# Candunio.net
KiCad netlist of a schematic drawn in Altium Designer
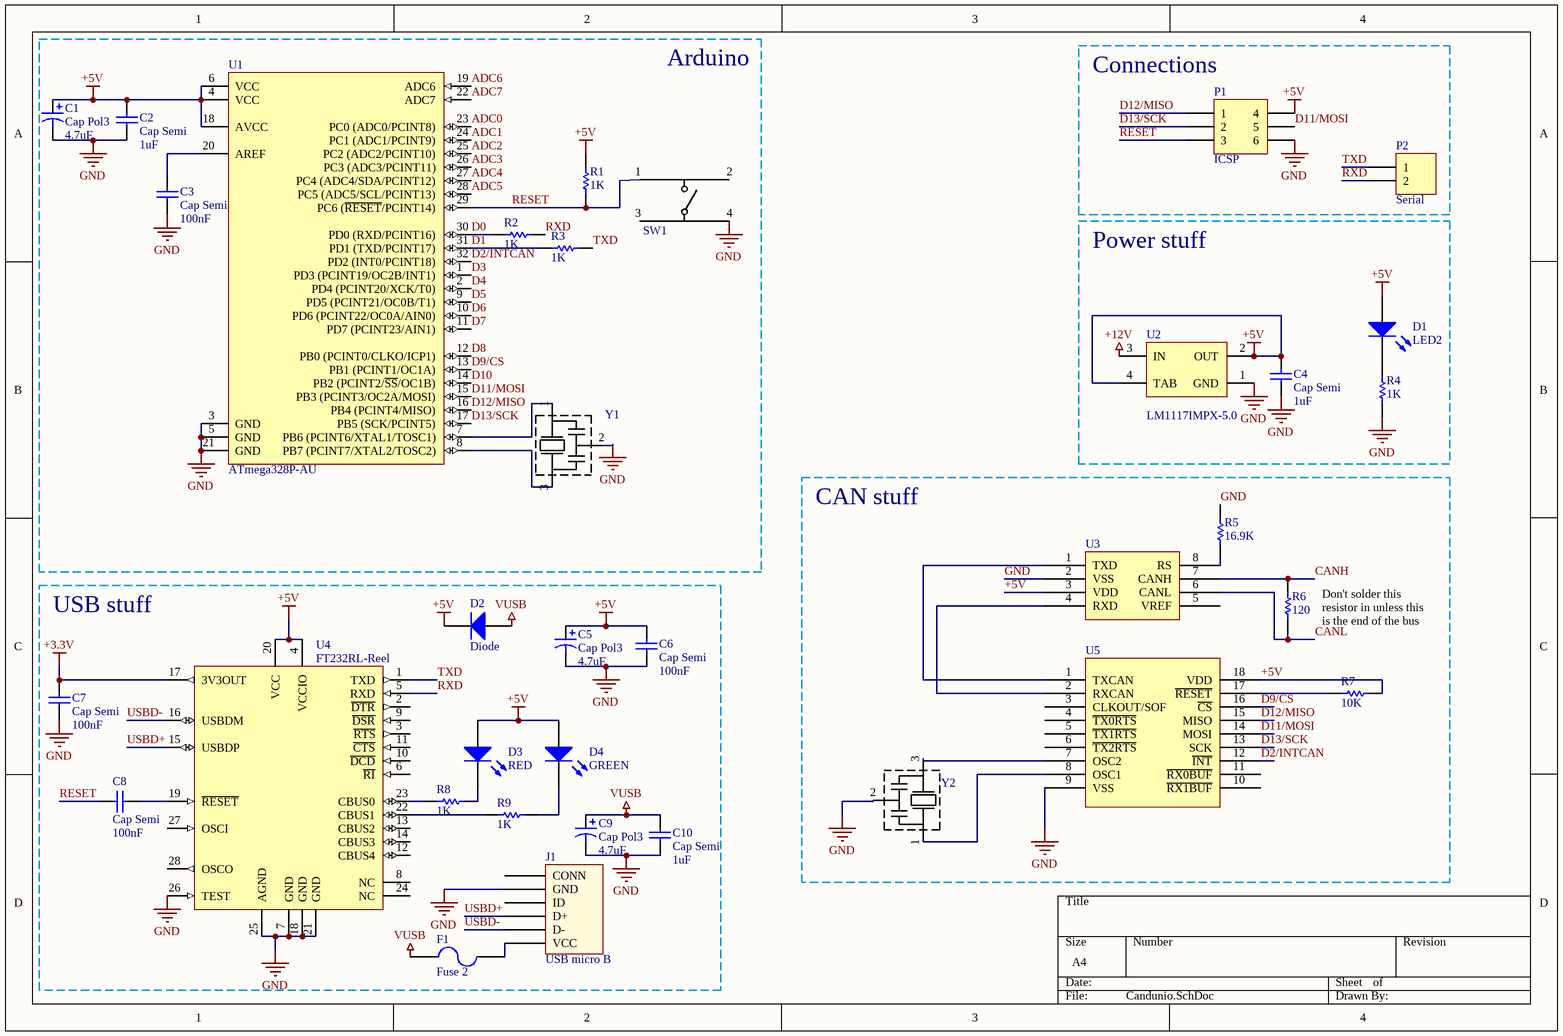
[diagram p0: Candunio.SchDoc]

(export (version "E")
  (design (tool "Eeschema 10.0.6"))
  (components
    (comp (ref "C1")
      (value "Cap Pol3")
      (footprint "C1206")
      (description "Polarized Capacitor (Surface Mount)")
      (fields (field (name "ALTIUM_VALUE") "4.7uF") (field (name "PUBLISHER") "Altium Limited"))
      (libsource (lib "Miscellaneous Devices") (part "Cap Pol3"))
    )
    (comp (ref "C2")
      (value "Cap Semi")
      (footprint "C1206")
      (description "Capacitor (Semiconductor SIM Model)")
      (fields (field (name "ALTIUM_VALUE") "1uF") (field (name "PUBLISHER") "Altium Limited"))
      (libsource (lib "Miscellaneous Devices") (part "Cap Semi"))
    )
    (comp (ref "C3")
      (value "Cap Semi")
      (footprint "C1206")
      (description "Capacitor (Semiconductor SIM Model)")
      (fields (field (name "ALTIUM_VALUE") "100nF") (field (name "PUBLISHER") "Altium Limited"))
      (libsource (lib "Miscellaneous Devices") (part "Cap Semi"))
    )
    (comp (ref "C4")
      (value "Cap Semi")
      (footprint "C1206")
      (description "Capacitor (Semiconductor SIM Model)")
      (fields (field (name "ALTIUM_VALUE") "1uF") (field (name "PUBLISHER") "Altium Limited"))
      (libsource (lib "Miscellaneous Devices") (part "Cap Semi"))
    )
    (comp (ref "C5")
      (value "Cap Pol3")
      (footprint "C1206")
      (description "Polarized Capacitor (Surface Mount)")
      (fields (field (name "ALTIUM_VALUE") "4.7uF") (field (name "PUBLISHER") "Altium Limited"))
      (libsource (lib "Miscellaneous Devices") (part "Cap Pol3"))
    )
    (comp (ref "C6")
      (value "Cap Semi")
      (footprint "C1206")
      (description "Capacitor (Semiconductor SIM Model)")
      (fields (field (name "ALTIUM_VALUE") "100nF") (field (name "PUBLISHER") "Altium Limited"))
      (libsource (lib "Miscellaneous Devices") (part "Cap Semi"))
    )
    (comp (ref "C7")
      (value "Cap Semi")
      (footprint "C1206")
      (description "Capacitor (Semiconductor SIM Model)")
      (fields (field (name "ALTIUM_VALUE") "100nF") (field (name "PUBLISHER") "Altium Limited"))
      (libsource (lib "Miscellaneous Devices") (part "Cap Semi"))
    )
    (comp (ref "C8")
      (value "Cap Semi")
      (footprint "C1206")
      (description "Capacitor (Semiconductor SIM Model)")
      (fields (field (name "ALTIUM_VALUE") "100nF") (field (name "PUBLISHER") "Altium Limited"))
      (libsource (lib "Miscellaneous Devices") (part "Cap Semi"))
    )
    (comp (ref "C9")
      (value "Cap Pol3")
      (footprint "C1206")
      (description "Polarized Capacitor (Surface Mount)")
      (fields (field (name "ALTIUM_VALUE") "4.7uF") (field (name "PUBLISHER") "Altium Limited"))
      (libsource (lib "Miscellaneous Devices") (part "Cap Pol3"))
    )
    (comp (ref "C10")
      (value "Cap Semi")
      (footprint "C1206")
      (description "Capacitor (Semiconductor SIM Model)")
      (fields (field (name "ALTIUM_VALUE") "1uF") (field (name "PUBLISHER") "Altium Limited"))
      (libsource (lib "Miscellaneous Devices") (part "Cap Semi"))
    )
    (comp (ref "D1")
      (value "LED2")
      (footprint "3.2X1.6X1.1")
      (description "Typical RED, GREEN, YELLOW, AMBER GaAs LED")
      (fields (field (name "PUBLISHER") "Altium Limited"))
      (libsource (lib "Miscellaneous Devices") (part "LED2"))
    )
    (comp (ref "D2")
      (value "Diode")
      (footprint "SMC")
      (description "Default Diode")
      (fields (field (name "PUBLISHER") "Altium Limited"))
      (libsource (lib "Miscellaneous Devices") (part "Diode"))
    )
    (comp (ref "D3")
      (value "RED")
      (footprint "3.2X1.6X1.1")
      (description "Typical RED, GREEN, YELLOW, AMBER GaAs LED")
      (fields (field (name "PUBLISHER") "Altium Limited"))
      (libsource (lib "Miscellaneous Devices") (part "LED2"))
    )
    (comp (ref "D4")
      (value "GREEN")
      (footprint "3.2X1.6X1.1")
      (description "Typical RED, GREEN, YELLOW, AMBER GaAs LED")
      (fields (field (name "PUBLISHER") "Altium Limited"))
      (libsource (lib "Miscellaneous Devices") (part "LED2"))
    )
    (comp (ref "F1")
      (value "Fuse 2")
      (footprint "1812")
      (description "Fuse")
      (fields (field (name "PART NUMBER") "MF-MSMF050-2") (field (name "PUBLISHER") "Altium Limited"))
      (libsource (lib "Miscellaneous Devices") (part "Fuse 2"))
    )
    (comp (ref "J1")
      (value "USB micro B")
      (footprint "1050170001")
      (description "CONN SM TH USB MICRO MODIFIED FOR DRILL")
      (fields (field (name "PART NUMBER") "WM1399CT-ND"))
      (libsource (lib "electronpowered") (part "1050170001"))
    )
    (comp (ref "P1")
      (value "ICSP")
      (footprint "HDR2X3_CEN")
      (description "Header, 3-Pin, Dual row")
      (fields (field (name "PUBLISHER") "Altium Limited"))
      (libsource (lib "Miscellaneous Connectors") (part "Header 3X2A"))
    )
    (comp (ref "P2")
      (value "Serial")
      (footprint "HDR1X2")
      (description "Header, 2-Pin")
      (fields (field (name "PUBLISHER") "Altium Limited"))
      (libsource (lib "Miscellaneous Connectors") (part "Header 2"))
    )
    (comp (ref "R1")
      (value "1K")
      (footprint "14-1210")
      (description "Resistor")
      (libsource (lib "Miscellaneous Devices") (part "Res1"))
    )
    (comp (ref "R2")
      (value "1K")
      (footprint "14-1210")
      (description "Resistor")
      (libsource (lib "Miscellaneous Devices") (part "Res1"))
    )
    (comp (ref "R3")
      (value "1K")
      (footprint "14-1210")
      (description "Resistor")
      (libsource (lib "Miscellaneous Devices") (part "Res1"))
    )
    (comp (ref "R4")
      (value "1K")
      (footprint "14-1210")
      (description "Resistor")
      (libsource (lib "Miscellaneous Devices") (part "Res1"))
    )
    (comp (ref "R5")
      (value "16.9K")
      (footprint "14-1210")
      (description "Resistor")
      (libsource (lib "Miscellaneous Devices") (part "Res1"))
    )
    (comp (ref "R6")
      (value "120")
      (footprint "14-1210")
      (description "Resistor")
      (libsource (lib "Miscellaneous Devices") (part "Res1"))
    )
    (comp (ref "R7")
      (value "10K")
      (footprint "14-1210")
      (description "Resistor")
      (libsource (lib "Miscellaneous Devices") (part "Res1"))
    )
    (comp (ref "R8")
      (value "1K")
      (footprint "14-1210")
      (description "Resistor")
      (libsource (lib "Miscellaneous Devices") (part "Res1"))
    )
    (comp (ref "R9")
      (value "1K")
      (footprint "14-1210")
      (description "Resistor")
      (libsource (lib "Miscellaneous Devices") (part "Res1"))
    )
    (comp (ref "SW1")
      (value "PTS525SM15SMTR2")
      (footprint "PTS525SM15SMTR2")
      (libsource (lib "AMSComponents") (part "PTS525SM15SMTR2"))
    )
    (comp (ref "U1")
      (value "ATmega328P-AU")
      (footprint "32A_N")
      (fields (field (name "PUBLISHER") "Altium Limited"))
      (libsource (lib "Atmel Microcontroller 8-Bit megaAVR") (part "ATmega328P-AU"))
    )
    (comp (ref "U2")
      (value "LM1117IMPX-5.0")
      (footprint "MP04A_N")
      (description "800mA Low-Dropout Linear Regulator, 4-pin SOT-223")
      (fields
        (field (name "MANUFACTURER") "National Semiconductor")
        (field (name "PUBLISHER") "Altium Limited")
      )
      (libsource (lib "NSC LDO") (part "LM1117IMPX-5.0"))
    )
    (comp (ref "U3")
      (value "MCP2551-E/SN")
      (footprint "SOIC127P600X175-8M")
      (description "SOIC")
      (libsource (lib "AMSComponents") (part "MCP2551-E/SN"))
    )
    (comp (ref "U4")
      (value "FT232RL-Reel")
      (footprint "SSOP-28_N")
      (description "USB UART Asynchronous Serial Data Transfer Chip, SSOP-28, Tape and Reel")
      (fields (field (name "PUBLISHER") "Altium Limited"))
      (libsource (lib "FTDI Communication UART") (part "FT232RL-Reel"))
    )
    (comp (ref "U5")
      (value "MCP2515-E/ST")
      (footprint "SOIC127P1030X265-18M")
      (description "SOIC")
      (libsource (lib "AMSComponents") (part "MCP2515-E/ST"))
    )
    (comp (ref "Y1")
      (value "CSTCE16M0V53-R0")
      (footprint "CSTCE16M0V53-R0")
      (libsource (lib "AMSComponents") (part "CSTCE16M0V53-R0"))
    )
    (comp (ref "Y2")
      (value "CSTCE16M0V53-R0")
      (footprint "CSTCE16M0V53-R0")
      (libsource (lib "AMSComponents") (part "CSTCE16M0V53-R0"))
    )
  )
  (nets
    (net (code "1") (name "+3.3V") (class "Default")
      (node (ref "C7") (pin "1") (pinfunction "1_1") (pintype "passive"))
      (node (ref "U4") (pin "17") (pinfunction "3V3OUT_17") (pintype "output"))
    )
    (net (code "2") (name "+5V") (class "Default")
      (node (ref "C1") (pin "1") (pinfunction "1_1") (pintype "passive"))
      (node (ref "C2") (pin "1") (pinfunction "1_1") (pintype "passive"))
      (node (ref "C4") (pin "1") (pinfunction "1_1") (pintype "passive"))
      (node (ref "C5") (pin "1") (pinfunction "1_1") (pintype "passive"))
      (node (ref "C6") (pin "1") (pinfunction "1_1") (pintype "passive"))
      (node (ref "D1") (pin "1") (pinfunction "A_1") (pintype "passive"))
      (node (ref "D2") (pin "2") (pinfunction "K_2") (pintype "passive"))
      (node (ref "D3") (pin "1") (pinfunction "A_1") (pintype "passive"))
      (node (ref "D4") (pin "1") (pinfunction "A_1") (pintype "passive"))
      (node (ref "P1") (pin "4") (pinfunction "4_4") (pintype "passive"))
      (node (ref "R1") (pin "1") (pinfunction "1_1") (pintype "passive"))
      (node (ref "R7") (pin "2") (pinfunction "2_2") (pintype "passive"))
      (node (ref "U1") (pin "18") (pinfunction "AVCC_18") (pintype "power_in"))
      (node (ref "U1") (pin "4") (pinfunction "VCC_4") (pintype "power_in"))
      (node (ref "U1") (pin "6") (pinfunction "VCC_6") (pintype "power_in"))
      (node (ref "U2") (pin "2") (pinfunction "OUT_2") (pintype "power_in"))
      (node (ref "U2") (pin "4") (pinfunction "TAB_4") (pintype "power_in"))
      (node (ref "U3") (pin "3") (pinfunction "VDD_3") (pintype "passive"))
      (node (ref "U4") (pin "20") (pinfunction "VCC_20") (pintype "power_in"))
      (node (ref "U4") (pin "4") (pinfunction "VCCIO_4") (pintype "power_in"))
      (node (ref "U5") (pin "18") (pinfunction "VDD_18") (pintype "passive"))
    )
    (net (code "3") (name "+12V") (class "Default")
      (node (ref "U2") (pin "3") (pinfunction "IN_3") (pintype "power_in"))
    )
    (net (code "4") (name "/ADC0") (class "Default")
      (node (ref "U1") (pin "23") (pinfunction "PC0_(ADC0/PCINT8)_23") (pintype "bidirectional"))
    )
    (net (code "5") (name "/ADC1") (class "Default")
      (node (ref "U1") (pin "24") (pinfunction "PC1_(ADC1/PCINT9)_24") (pintype "bidirectional"))
    )
    (net (code "6") (name "/ADC2") (class "Default")
      (node (ref "U1") (pin "25") (pinfunction "PC2_(ADC2/PCINT10)_25") (pintype "bidirectional"))
    )
    (net (code "7") (name "/ADC3") (class "Default")
      (node (ref "U1") (pin "26") (pinfunction "PC3_(ADC3/PCINT11)_26") (pintype "bidirectional"))
    )
    (net (code "8") (name "/ADC4") (class "Default")
      (node (ref "U1") (pin "27") (pinfunction "PC4_(ADC4/SDA/PCINT12)_27") (pintype "bidirectional"))
    )
    (net (code "9") (name "/ADC5") (class "Default")
      (node (ref "U1") (pin "28") (pinfunction "PC5_(ADC5/SCL/PCINT13)_28") (pintype "bidirectional"))
    )
    (net (code "10") (name "/ADC6") (class "Default")
      (node (ref "U1") (pin "19") (pinfunction "ADC6_19") (pintype "input"))
    )
    (net (code "11") (name "/ADC7") (class "Default")
      (node (ref "U1") (pin "22") (pinfunction "ADC7_22") (pintype "input"))
    )
    (net (code "12") (name "/CANH") (class "Default")
      (node (ref "R6") (pin "1") (pinfunction "1_1") (pintype "passive"))
      (node (ref "U3") (pin "7") (pinfunction "CANH_7") (pintype "passive"))
    )
    (net (code "13") (name "/CANL") (class "Default")
      (node (ref "R6") (pin "2") (pinfunction "2_2") (pintype "passive"))
      (node (ref "U3") (pin "6") (pinfunction "CANL_6") (pintype "passive"))
    )
    (net (code "14") (name "/D0") (class "Default")
      (node (ref "R2") (pin "1") (pinfunction "1_1") (pintype "passive"))
      (node (ref "U1") (pin "30") (pinfunction "PD0_(RXD/PCINT16)_30") (pintype "bidirectional"))
    )
    (net (code "15") (name "/D1") (class "Default")
      (node (ref "R3") (pin "1") (pinfunction "1_1") (pintype "passive"))
      (node (ref "U1") (pin "31") (pinfunction "PD1_(TXD/PCINT17)_31") (pintype "bidirectional"))
    )
    (net (code "16") (name "/D2{slash}INTCAN") (class "Default")
      (node (ref "U1") (pin "32") (pinfunction "PD2_(INT0/PCINT18)_32") (pintype "bidirectional"))
      (node (ref "U5") (pin "12") (pinfunction "~{INT}_12") (pintype "passive"))
    )
    (net (code "17") (name "/D3") (class "Default")
      (node (ref "U1") (pin "1") (pinfunction "PD3_(PCINT19/OC2B/INT1)_1") (pintype "bidirectional"))
    )
    (net (code "18") (name "/D4") (class "Default")
      (node (ref "U1") (pin "2") (pinfunction "PD4_(PCINT20/XCK/T0)_2") (pintype "bidirectional"))
    )
    (net (code "19") (name "/D5") (class "Default")
      (node (ref "U1") (pin "9") (pinfunction "PD5_(PCINT21/OC0B/T1)_9") (pintype "bidirectional"))
    )
    (net (code "20") (name "/D6") (class "Default")
      (node (ref "U1") (pin "10") (pinfunction "PD6_(PCINT22/OC0A/AIN0)_10") (pintype "bidirectional"))
    )
    (net (code "21") (name "/D7") (class "Default")
      (node (ref "U1") (pin "11") (pinfunction "PD7_(PCINT23/AIN1)_11") (pintype "bidirectional"))
    )
    (net (code "22") (name "/D8") (class "Default")
      (node (ref "U1") (pin "12") (pinfunction "PB0_(PCINT0/CLKO/ICP1)_12") (pintype "bidirectional"))
    )
    (net (code "23") (name "/D9{slash}CS") (class "Default")
      (node (ref "U1") (pin "13") (pinfunction "PB1_(PCINT1/OC1A)_13") (pintype "bidirectional"))
      (node (ref "U5") (pin "16") (pinfunction "~{CS}_16") (pintype "passive"))
    )
    (net (code "24") (name "/D10") (class "Default")
      (node (ref "U1") (pin "14") (pinfunction "PB2_(PCINT2/~{SS}/OC1B)_14") (pintype "bidirectional"))
    )
    (net (code "25") (name "/D11{slash}MOSI") (class "Default")
      (node (ref "P1") (pin "5") (pinfunction "5_5") (pintype "passive"))
      (node (ref "U1") (pin "15") (pinfunction "PB3_(PCINT3/OC2A/MOSI)_15") (pintype "bidirectional"))
      (node (ref "U5") (pin "14") (pinfunction "MOSI_14") (pintype "passive"))
    )
    (net (code "26") (name "/D12{slash}MISO") (class "Default")
      (node (ref "P1") (pin "1") (pinfunction "1_1") (pintype "passive"))
      (node (ref "U1") (pin "16") (pinfunction "PB4_(PCINT4/MISO)_16") (pintype "bidirectional"))
      (node (ref "U5") (pin "15") (pinfunction "MISO_15") (pintype "passive"))
    )
    (net (code "27") (name "/D13{slash}SCK") (class "Default")
      (node (ref "P1") (pin "2") (pinfunction "2_2") (pintype "passive"))
      (node (ref "U1") (pin "17") (pinfunction "PB5_(SCK/PCINT5)_17") (pintype "bidirectional"))
      (node (ref "U5") (pin "13") (pinfunction "SCK_13") (pintype "passive"))
    )
    (net (code "28") (name "/RESET") (class "Default")
      (node (ref "C8") (pin "1") (pinfunction "1_1") (pintype "passive"))
      (node (ref "P1") (pin "3") (pinfunction "3_3") (pintype "passive"))
      (node (ref "R1") (pin "2") (pinfunction "2_2") (pintype "passive"))
      (node (ref "SW1") (pin "1") (pinfunction "1_1") (pintype "passive"))
      (node (ref "U1") (pin "29") (pinfunction "PC6_(~{RESET}/PCINT14)_29") (pintype "bidirectional"))
    )
    (net (code "29") (name "/RXD") (class "Default")
      (node (ref "P2") (pin "2") (pinfunction "2_2") (pintype "passive"))
      (node (ref "R2") (pin "2") (pinfunction "2_2") (pintype "passive"))
      (node (ref "U4") (pin "5") (pinfunction "RXD_5") (pintype "input"))
    )
    (net (code "30") (name "/TXD") (class "Default")
      (node (ref "P2") (pin "1") (pinfunction "1_1") (pintype "passive"))
      (node (ref "R3") (pin "2") (pinfunction "2_2") (pintype "passive"))
      (node (ref "U4") (pin "1") (pinfunction "TXD_1") (pintype "output"))
    )
    (net (code "31") (name "/USBD+") (class "Default")
      (node (ref "J1") (pin "3") (pinfunction "D+_3") (pintype "passive"))
      (node (ref "U4") (pin "15") (pinfunction "USBDP_15") (pintype "bidirectional"))
    )
    (net (code "32") (name "/USBD-") (class "Default")
      (node (ref "J1") (pin "2") (pinfunction "D-_2") (pintype "passive"))
      (node (ref "U4") (pin "16") (pinfunction "USBDM_16") (pintype "bidirectional"))
    )
    (net (code "33") (name "GND") (class "Default")
      (node (ref "C1") (pin "2") (pinfunction "2_2") (pintype "passive"))
      (node (ref "C10") (pin "2") (pinfunction "2_2") (pintype "passive"))
      (node (ref "C2") (pin "2") (pinfunction "2_2") (pintype "passive"))
      (node (ref "C3") (pin "2") (pinfunction "2_2") (pintype "passive"))
      (node (ref "C4") (pin "2") (pinfunction "2_2") (pintype "passive"))
      (node (ref "C5") (pin "2") (pinfunction "2_2") (pintype "passive"))
      (node (ref "C6") (pin "2") (pinfunction "2_2") (pintype "passive"))
      (node (ref "C7") (pin "2") (pinfunction "2_2") (pintype "passive"))
      (node (ref "C9") (pin "2") (pinfunction "2_2") (pintype "passive"))
      (node (ref "J1") (pin "5") (pinfunction "GND_5") (pintype "passive"))
      (node (ref "P1") (pin "6") (pinfunction "6_6") (pintype "passive"))
      (node (ref "R4") (pin "2") (pinfunction "2_2") (pintype "passive"))
      (node (ref "R5") (pin "1") (pinfunction "1_1") (pintype "passive"))
      (node (ref "SW1") (pin "4") (pinfunction "4_4") (pintype "passive"))
      (node (ref "U1") (pin "21") (pinfunction "GND_21") (pintype "power_in"))
      (node (ref "U1") (pin "3") (pinfunction "GND_3") (pintype "power_in"))
      (node (ref "U1") (pin "5") (pinfunction "GND_5") (pintype "power_in"))
      (node (ref "U2") (pin "1") (pinfunction "GND_1") (pintype "power_in"))
      (node (ref "U3") (pin "2") (pinfunction "VSS_2") (pintype "passive"))
      (node (ref "U4") (pin "18") (pinfunction "GND_18") (pintype "power_in"))
      (node (ref "U4") (pin "21") (pinfunction "GND_21") (pintype "power_in"))
      (node (ref "U4") (pin "25") (pinfunction "AGND_25") (pintype "power_in"))
      (node (ref "U4") (pin "26") (pinfunction "TEST_26") (pintype "input"))
      (node (ref "U4") (pin "7") (pinfunction "GND_7") (pintype "power_in"))
      (node (ref "U5") (pin "9") (pinfunction "VSS_9") (pintype "passive"))
      (node (ref "Y1") (pin "2") (pinfunction "2_2") (pintype "passive"))
      (node (ref "Y2") (pin "2") (pinfunction "2_2") (pintype "passive"))
    )
    (net (code "34") (name "Net-(D1-K)") (class "Default")
      (node (ref "D1") (pin "2") (pinfunction "K_2") (pintype "passive"))
      (node (ref "R4") (pin "1") (pinfunction "1_1") (pintype "passive"))
    )
    (net (code "35") (name "Net-(D3-K)") (class "Default")
      (node (ref "D3") (pin "2") (pinfunction "K_2") (pintype "passive"))
      (node (ref "R8") (pin "2") (pinfunction "2_2") (pintype "passive"))
    )
    (net (code "36") (name "Net-(D4-K)") (class "Default")
      (node (ref "D4") (pin "2") (pinfunction "K_2") (pintype "passive"))
      (node (ref "R9") (pin "2") (pinfunction "2_2") (pintype "passive"))
    )
    (net (code "37") (name "Net-(J1-VCC)") (class "Default")
      (node (ref "F1") (pin "2") (pinfunction "2_2") (pintype "passive"))
      (node (ref "J1") (pin "1") (pinfunction "VCC_1") (pintype "passive"))
    )
    (net (code "38") (name "Net-(U1-AREF)") (class "Default")
      (node (ref "C3") (pin "1") (pinfunction "1_1") (pintype "passive"))
      (node (ref "U1") (pin "20") (pinfunction "AREF_20") (pintype "passive"))
    )
    (net (code "39") (name "Net-(U1-PB6_(PCINT6{slash}XTAL1{slash}TOSC1))") (class "Default")
      (node (ref "U1") (pin "7") (pinfunction "PB6_(PCINT6/XTAL1/TOSC1)_7") (pintype "bidirectional"))
      (node (ref "Y1") (pin "1") (pinfunction "1_1") (pintype "passive"))
    )
    (net (code "40") (name "Net-(U1-PB7_(PCINT7{slash}XTAL2{slash}TOSC2))") (class "Default")
      (node (ref "U1") (pin "8") (pinfunction "PB7_(PCINT7/XTAL2/TOSC2)_8") (pintype "bidirectional"))
      (node (ref "Y1") (pin "3") (pinfunction "3_3") (pintype "passive"))
    )
    (net (code "41") (name "Net-(U3-RS)") (class "Default")
      (node (ref "R5") (pin "2") (pinfunction "2_2") (pintype "passive"))
      (node (ref "U3") (pin "8") (pinfunction "RS_8") (pintype "passive"))
    )
    (net (code "42") (name "Net-(U3-RXD)") (class "Default")
      (node (ref "U3") (pin "4") (pinfunction "RXD_4") (pintype "passive"))
      (node (ref "U5") (pin "2") (pinfunction "RXCAN_2") (pintype "passive"))
    )
    (net (code "43") (name "Net-(U3-TXD)") (class "Default")
      (node (ref "U3") (pin "1") (pinfunction "TXD_1") (pintype "passive"))
      (node (ref "U5") (pin "1") (pinfunction "TXCAN_1") (pintype "passive"))
    )
    (net (code "44") (name "Net-(U4-CBUS0)") (class "Default")
      (node (ref "R8") (pin "1") (pinfunction "1_1") (pintype "passive"))
      (node (ref "U4") (pin "23") (pinfunction "CBUS0_23") (pintype "bidirectional"))
    )
    (net (code "45") (name "Net-(U4-CBUS1)") (class "Default")
      (node (ref "R9") (pin "1") (pinfunction "1_1") (pintype "passive"))
      (node (ref "U4") (pin "22") (pinfunction "CBUS1_22") (pintype "bidirectional"))
    )
    (net (code "46") (name "Net-(U4-~{RESET})") (class "Default")
      (node (ref "C8") (pin "2") (pinfunction "2_2") (pintype "passive"))
      (node (ref "U4") (pin "19") (pinfunction "~{RESET}_19") (pintype "input"))
    )
    (net (code "47") (name "Net-(U5-OSC1)") (class "Default")
      (node (ref "U5") (pin "8") (pinfunction "OSC1_8") (pintype "passive"))
      (node (ref "Y2") (pin "1") (pinfunction "1_1") (pintype "passive"))
    )
    (net (code "48") (name "Net-(U5-OSC2)") (class "Default")
      (node (ref "U5") (pin "7") (pinfunction "OSC2_7") (pintype "passive"))
      (node (ref "Y2") (pin "3") (pinfunction "3_3") (pintype "passive"))
    )
    (net (code "49") (name "Net-(U5-~{RESET})") (class "Default")
      (node (ref "R7") (pin "1") (pinfunction "1_1") (pintype "passive"))
      (node (ref "U5") (pin "17") (pinfunction "~{RESET}_17") (pintype "passive"))
    )
    (net (code "50") (name "VUSB") (class "Default")
      (node (ref "C10") (pin "1") (pinfunction "1_1") (pintype "passive"))
      (node (ref "C9") (pin "1") (pinfunction "1_1") (pintype "passive"))
      (node (ref "D2") (pin "1") (pinfunction "A_1") (pintype "passive"))
      (node (ref "F1") (pin "1") (pinfunction "1_1") (pintype "passive"))
    )
    (net (code "51") (name "unconnected-(J1-CONN-Pad0)") (class "Default")
      (node (ref "J1") (pin "0") (pinfunction "CONN_0") (pintype "passive"))
    )
    (net (code "52") (name "unconnected-(J1-ID-Pad4)") (class "Default")
      (node (ref "J1") (pin "4") (pinfunction "ID_4") (pintype "passive"))
    )
    (net (code "53") (name "unconnected-(SW1-Pad2)") (class "Default")
      (node (ref "SW1") (pin "2") (pinfunction "2_2") (pintype "passive"))
    )
    (net (code "54") (name "unconnected-(SW1-Pad3)") (class "Default")
      (node (ref "SW1") (pin "3") (pinfunction "3_3") (pintype "passive"))
    )
    (net (code "55") (name "unconnected-(U3-VREF-Pad5)") (class "Default")
      (node (ref "U3") (pin "5") (pinfunction "VREF_5") (pintype "passive"))
    )
    (net (code "56") (name "unconnected-(U4-CBUS2-Pad13)") (class "Default")
      (node (ref "U4") (pin "13") (pinfunction "CBUS2_13") (pintype "bidirectional"))
    )
    (net (code "57") (name "unconnected-(U4-CBUS3-Pad14)") (class "Default")
      (node (ref "U4") (pin "14") (pinfunction "CBUS3_14") (pintype "bidirectional"))
    )
    (net (code "58") (name "unconnected-(U4-CBUS4-Pad12)") (class "Default")
      (node (ref "U4") (pin "12") (pinfunction "CBUS4_12") (pintype "bidirectional"))
    )
    (net (code "59") (name "unconnected-(U4-NC-Pad8)") (class "Default")
      (node (ref "U4") (pin "8") (pinfunction "NC_8") (pintype "passive"))
    )
    (net (code "60") (name "unconnected-(U4-NC-Pad24)") (class "Default")
      (node (ref "U4") (pin "24") (pinfunction "NC_24") (pintype "passive"))
    )
    (net (code "61") (name "unconnected-(U4-OSCI-Pad27)") (class "Default")
      (node (ref "U4") (pin "27") (pinfunction "OSCI_27") (pintype "input"))
    )
    (net (code "62") (name "unconnected-(U4-OSCO-Pad28)") (class "Default")
      (node (ref "U4") (pin "28") (pinfunction "OSCO_28") (pintype "output"))
    )
    (net (code "63") (name "unconnected-(U4-~{CTS}-Pad11)") (class "Default")
      (node (ref "U4") (pin "11") (pinfunction "~{CTS}_11") (pintype "input"))
    )
    (net (code "64") (name "unconnected-(U4-~{DCD}-Pad10)") (class "Default")
      (node (ref "U4") (pin "10") (pinfunction "~{DCD}_10") (pintype "input"))
    )
    (net (code "65") (name "unconnected-(U4-~{DSR}-Pad9)") (class "Default")
      (node (ref "U4") (pin "9") (pinfunction "~{DSR}_9") (pintype "input"))
    )
    (net (code "66") (name "unconnected-(U4-~{DTR}-Pad2)") (class "Default")
      (node (ref "U4") (pin "2") (pinfunction "~{DTR}_2") (pintype "output"))
    )
    (net (code "67") (name "unconnected-(U4-~{RI}-Pad6)") (class "Default")
      (node (ref "U4") (pin "6") (pinfunction "~{RI}_6") (pintype "input"))
    )
    (net (code "68") (name "unconnected-(U4-~{RTS}-Pad3)") (class "Default")
      (node (ref "U4") (pin "3") (pinfunction "~{RTS}_3") (pintype "output"))
    )
    (net (code "69") (name "unconnected-(U5-CLKOUT{slash}SOF-Pad3)") (class "Default")
      (node (ref "U5") (pin "3") (pinfunction "CLKOUT/SOF_3") (pintype "passive"))
    )
    (net (code "70") (name "unconnected-(U5-~{RX0BUF}-Pad11)") (class "Default")
      (node (ref "U5") (pin "11") (pinfunction "~{RX0BUF}_11") (pintype "passive"))
    )
    (net (code "71") (name "unconnected-(U5-~{RX1BUF}-Pad10)") (class "Default")
      (node (ref "U5") (pin "10") (pinfunction "~{RX1BUF}_10") (pintype "passive"))
    )
    (net (code "72") (name "unconnected-(U5-~{TX0RTS}-Pad4)") (class "Default")
      (node (ref "U5") (pin "4") (pinfunction "~{TX0RTS}_4") (pintype "passive"))
    )
    (net (code "73") (name "unconnected-(U5-~{TX1RTS}-Pad5)") (class "Default")
      (node (ref "U5") (pin "5") (pinfunction "~{TX1RTS}_5") (pintype "passive"))
    )
    (net (code "74") (name "unconnected-(U5-~{TX2RTS}-Pad6)") (class "Default")
      (node (ref "U5") (pin "6") (pinfunction "~{TX2RTS}_6") (pintype "passive"))
    )
  )
)
